# McPiFace-60mmFan-V3.net
KiCad netlist of a schematic drawn in EAGLE
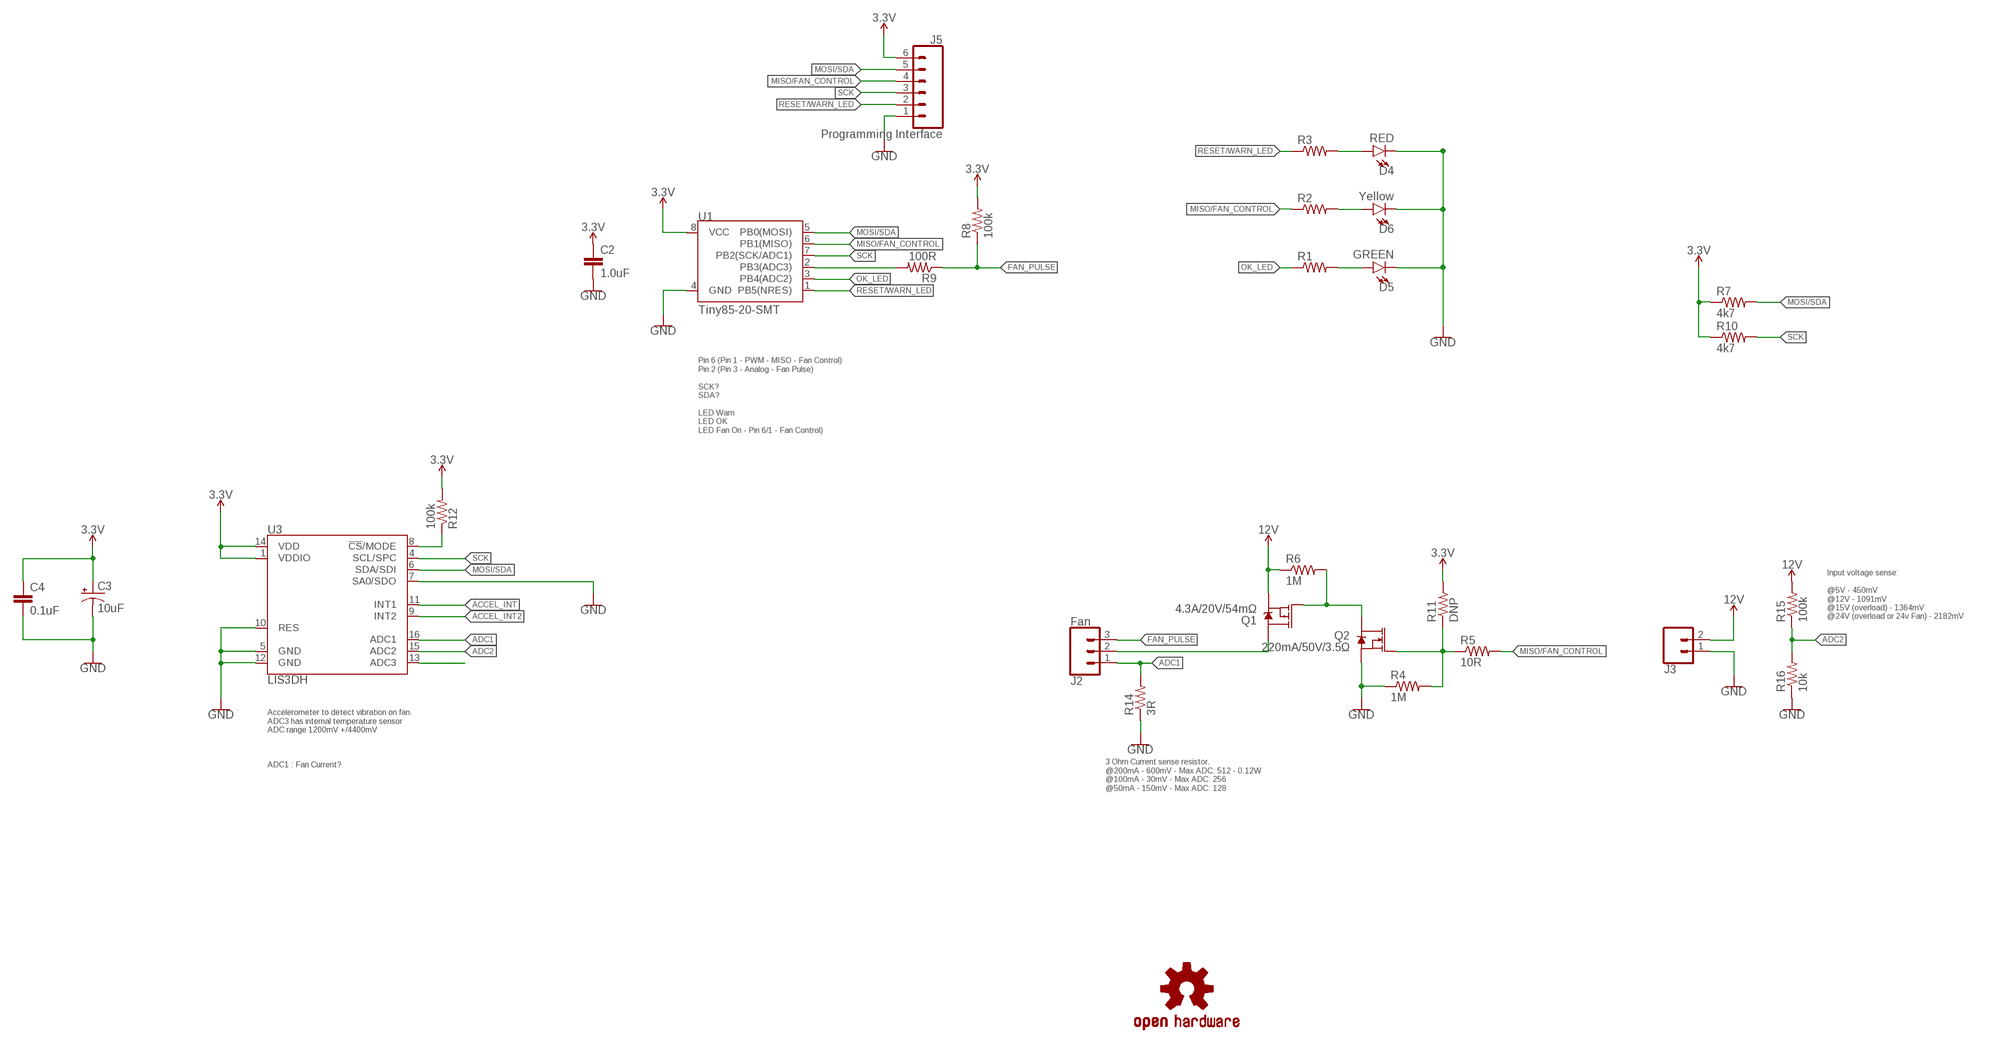
[diagram p0: schematic, sheet 1]

(export (version "E")
  (design (tool "Eeschema 10.0.6"))
  (components
    (comp (ref "C2")
      (value "1.0uF")
      (footprint "eagle-import:0805")
      (libsource (lib "eagle-import") (part "1.0UF-0805-25V-10%"))
    )
    (comp (ref "C3")
      (value "10uF")
      (footprint "eagle-import:EIA3216")
      (libsource (lib "eagle-import") (part "10UF-16V-10%(TANT)"))
    )
    (comp (ref "C4")
      (value "0.1uF")
      (footprint "eagle-import:0805")
      (libsource (lib "eagle-import") (part "1.0UF-0805-25V-10%"))
    )
    (comp (ref "D4")
      (value "RED")
      (footprint "eagle-import:LED-1206")
      (libsource (lib "eagle-import") (part "LED-RED1206"))
    )
    (comp (ref "D5")
      (value "GREEN")
      (footprint "eagle-import:LED-1206")
      (libsource (lib "eagle-import") (part "LED-GREEN1206"))
    )
    (comp (ref "D6")
      (value "Yellow")
      (footprint "eagle-import:LED-1206")
      (libsource (lib "eagle-import") (part "LED-YELLOWLILYPAD"))
    )
    (comp (ref "J2")
      (value "Fan")
      (footprint "eagle-import:JST-3-SMD")
      (fields (field (name "MFG") "S3B-PH-SM4-TB(LF)(SN)"))
      (libsource (lib "eagle-import") (part "CONN_03JST-SMD"))
    )
    (comp (ref "J3")
      (value "CONN_02-JST-2MM-SMT")
      (footprint "eagle-import:JST-2-SMD")
      (fields (field (name "MFG") "S2B-PH-SM4-TB(LF)(SN)"))
      (libsource (lib "eagle-import") (part "CONN_02-JST-2MM-SMT"))
    )
    (comp (ref "J5")
      (value "Programming Interface")
      (footprint "eagle-import:1X06-1MM")
      (libsource (lib "eagle-import") (part "CONN_06SMD-1MM"))
    )
    (comp (ref "LOGO1")
      (value "OSHW-LOGOL")
      (footprint "eagle-import:OSHW-LOGO-L")
      (libsource (lib "eagle-import") (part "OSHW-LOGOL"))
    )
    (comp (ref "Q1")
      (value "4.3A/20V/54mΩ")
      (footprint "eagle-import:SOT23-3")
      (libsource (lib "eagle-import") (part "MOSFET_PCH-IRLML2244"))
    )
    (comp (ref "Q2")
      (value "220mA/50V/3.5Ω")
      (footprint "eagle-import:SOT23-3")
      (libsource (lib "eagle-import") (part "MOSFET-NCH-BSS138"))
    )
    (comp (ref "R1")
      (value "RESISTOR0805-RES")
      (footprint "eagle-import:0805")
      (libsource (lib "eagle-import") (part "RESISTOR0805-RES"))
    )
    (comp (ref "R2")
      (value "RESISTOR0805-RES")
      (footprint "eagle-import:0805")
      (libsource (lib "eagle-import") (part "RESISTOR0805-RES"))
    )
    (comp (ref "R3")
      (value "RESISTOR0805-RES")
      (footprint "eagle-import:0805")
      (libsource (lib "eagle-import") (part "RESISTOR0805-RES"))
    )
    (comp (ref "R4")
      (value "1M")
      (footprint "eagle-import:0805")
      (libsource (lib "eagle-import") (part "RESISTOR0805-RES"))
    )
    (comp (ref "R5")
      (value "10R")
      (footprint "eagle-import:0805")
      (libsource (lib "eagle-import") (part "RESISTOR0805-RES"))
    )
    (comp (ref "R6")
      (value "1M")
      (footprint "eagle-import:0805")
      (libsource (lib "eagle-import") (part "RESISTOR0805-RES"))
    )
    (comp (ref "R7")
      (value "4k7")
      (footprint "eagle-import:0805")
      (libsource (lib "eagle-import") (part "RESISTOR0805-RES"))
    )
    (comp (ref "R8")
      (value "100k")
      (footprint "eagle-import:0805")
      (libsource (lib "eagle-import") (part "RESISTOR0805-RES"))
    )
    (comp (ref "R9")
      (value "100R")
      (footprint "eagle-import:0805")
      (libsource (lib "eagle-import") (part "RESISTOR0805-RES"))
    )
    (comp (ref "R10")
      (value "4k7")
      (footprint "eagle-import:0805")
      (libsource (lib "eagle-import") (part "RESISTOR0805-RES"))
    )
    (comp (ref "R11")
      (value "DNP")
      (footprint "eagle-import:0805")
      (libsource (lib "eagle-import") (part "RESISTOR0805-RES"))
    )
    (comp (ref "R12")
      (value "100k")
      (footprint "eagle-import:0805")
      (libsource (lib "eagle-import") (part "RESISTOR0805-RES"))
    )
    (comp (ref "R14")
      (value "3R")
      (footprint "eagle-import:0805")
      (libsource (lib "eagle-import") (part "RESISTOR0805-RES"))
    )
    (comp (ref "R15")
      (value "100k")
      (footprint "eagle-import:0805")
      (libsource (lib "eagle-import") (part "RESISTOR0805-RES"))
    )
    (comp (ref "R16")
      (value "10k")
      (footprint "eagle-import:0805")
      (libsource (lib "eagle-import") (part "RESISTOR0805-RES"))
    )
    (comp (ref "U1")
      (value "Tiny85-20-SMT")
      (footprint "eagle-import:SO08-EIAJ")
      (libsource (lib "eagle-import") (part "ATTINY45TINY85-20-SMT"))
    )
    (comp (ref "U3")
      (value "LIS3DH")
      (footprint "eagle-import:LGA-16-3X3")
      (libsource (lib "eagle-import") (part "LIS3DH"))
    )
  )
  (nets
    (net (code "1") (name "3.3V") (class "Default")
      (node (ref "C2") (pin "1") (pinfunction "1_1") (pintype "passive"))
      (node (ref "C3") (pin "A") (pinfunction "+_A") (pintype "passive"))
      (node (ref "C4") (pin "1") (pinfunction "1_1") (pintype "passive"))
      (node (ref "J5") (pin "6") (pinfunction "6_6") (pintype "passive"))
      (node (ref "R10") (pin "1") (pinfunction "1_1") (pintype "passive"))
      (node (ref "R11") (pin "2") (pinfunction "2_2") (pintype "passive"))
      (node (ref "R12") (pin "2") (pinfunction "2_2") (pintype "passive"))
      (node (ref "R7") (pin "1") (pinfunction "1_1") (pintype "passive"))
      (node (ref "R8") (pin "2") (pinfunction "2_2") (pintype "passive"))
      (node (ref "U1") (pin "8") (pinfunction "VCC_8") (pintype "bidirectional"))
      (node (ref "U3") (pin "1") (pinfunction "VDDIO_1") (pintype "bidirectional"))
      (node (ref "U3") (pin "14") (pinfunction "VDD_14") (pintype "bidirectional"))
    )
    (net (code "2") (name "12V") (class "Default")
      (node (ref "J3") (pin "2") (pinfunction "1_2") (pintype "passive"))
      (node (ref "Q1") (pin "2") (pinfunction "S_2") (pintype "bidirectional"))
      (node (ref "R15") (pin "2") (pinfunction "2_2") (pintype "passive"))
      (node (ref "R6") (pin "1") (pinfunction "1_1") (pintype "passive"))
    )
    (net (code "3") (name "ACCEL_INT") (class "Default")
      (node (ref "U3") (pin "11") (pinfunction "INT1_11") (pintype "bidirectional"))
    )
    (net (code "4") (name "ACCEL_INT2") (class "Default")
      (node (ref "U3") (pin "9") (pinfunction "INT2_9") (pintype "bidirectional"))
    )
    (net (code "5") (name "ADC1") (class "Default")
      (node (ref "J2") (pin "1") (pinfunction "3_1") (pintype "passive"))
      (node (ref "R14") (pin "2") (pinfunction "2_2") (pintype "passive"))
      (node (ref "U3") (pin "16") (pinfunction "ADC1_16") (pintype "bidirectional"))
    )
    (net (code "6") (name "ADC2") (class "Default")
      (node (ref "R15") (pin "1") (pinfunction "1_1") (pintype "passive"))
      (node (ref "R16") (pin "2") (pinfunction "2_2") (pintype "passive"))
      (node (ref "U3") (pin "15") (pinfunction "ADC2_15") (pintype "bidirectional"))
    )
    (net (code "7") (name "FAN_PULSE") (class "Default")
      (node (ref "J2") (pin "3") (pinfunction "1_3") (pintype "passive"))
      (node (ref "R8") (pin "1") (pinfunction "1_1") (pintype "passive"))
      (node (ref "R9") (pin "1") (pinfunction "1_1") (pintype "passive"))
    )
    (net (code "8") (name "GND") (class "Default")
      (node (ref "C2") (pin "2") (pinfunction "2_2") (pintype "passive"))
      (node (ref "C3") (pin "C") (pinfunction "-_C") (pintype "passive"))
      (node (ref "C4") (pin "2") (pinfunction "2_2") (pintype "passive"))
      (node (ref "D4") (pin "C") (pinfunction "C_C") (pintype "passive"))
      (node (ref "D5") (pin "C") (pinfunction "C_C") (pintype "passive"))
      (node (ref "D6") (pin "C") (pinfunction "C_C") (pintype "passive"))
      (node (ref "J3") (pin "1") (pinfunction "2_1") (pintype "passive"))
      (node (ref "J5") (pin "1") (pinfunction "1_1") (pintype "passive"))
      (node (ref "Q2") (pin "2") (pinfunction "S_2") (pintype "bidirectional"))
      (node (ref "R14") (pin "1") (pinfunction "1_1") (pintype "passive"))
      (node (ref "R16") (pin "1") (pinfunction "1_1") (pintype "passive"))
      (node (ref "R4") (pin "1") (pinfunction "1_1") (pintype "passive"))
      (node (ref "U1") (pin "4") (pinfunction "GND_4") (pintype "bidirectional"))
      (node (ref "U3") (pin "10") (pinfunction "RES_10") (pintype "bidirectional"))
      (node (ref "U3") (pin "12") (pinfunction "GND_12") (pintype "bidirectional"))
      (node (ref "U3") (pin "5") (pinfunction "GND_5") (pintype "bidirectional"))
      (node (ref "U3") (pin "7") (pinfunction "SA0/SDO_7") (pintype "bidirectional"))
    )
    (net (code "9") (name "MISO{slash}FAN_CONTROL") (class "Default")
      (node (ref "J5") (pin "4") (pinfunction "4_4") (pintype "passive"))
      (node (ref "R2") (pin "1") (pinfunction "1_1") (pintype "passive"))
      (node (ref "R5") (pin "2") (pinfunction "2_2") (pintype "passive"))
      (node (ref "U1") (pin "6") (pinfunction "PB1(MISO)_6") (pintype "bidirectional"))
    )
    (net (code "10") (name "MOSI{slash}SDA") (class "Default")
      (node (ref "J5") (pin "5") (pinfunction "5_5") (pintype "passive"))
      (node (ref "R7") (pin "2") (pinfunction "2_2") (pintype "passive"))
      (node (ref "U1") (pin "5") (pinfunction "PB0(MOSI)_5") (pintype "bidirectional"))
      (node (ref "U3") (pin "6") (pinfunction "SDA/SDI_6") (pintype "bidirectional"))
    )
    (net (code "11") (name "Net-(D4-PadA)") (class "Default")
      (node (ref "D4") (pin "A") (pinfunction "A_A") (pintype "passive"))
      (node (ref "R3") (pin "2") (pinfunction "2_2") (pintype "passive"))
    )
    (net (code "12") (name "Net-(D5-PadA)") (class "Default")
      (node (ref "D5") (pin "A") (pinfunction "A_A") (pintype "passive"))
      (node (ref "R1") (pin "2") (pinfunction "2_2") (pintype "passive"))
    )
    (net (code "13") (name "Net-(D6-PadA)") (class "Default")
      (node (ref "D6") (pin "A") (pinfunction "A_A") (pintype "passive"))
      (node (ref "R2") (pin "2") (pinfunction "2_2") (pintype "passive"))
    )
    (net (code "14") (name "Net-(Q1-D)") (class "Default")
      (node (ref "J2") (pin "2") (pinfunction "2_2") (pintype "passive"))
      (node (ref "Q1") (pin "3") (pinfunction "D_3") (pintype "bidirectional"))
    )
    (net (code "15") (name "Net-(Q1-G)") (class "Default")
      (node (ref "Q1") (pin "1") (pinfunction "G_1") (pintype "bidirectional"))
      (node (ref "Q2") (pin "3") (pinfunction "D_3") (pintype "bidirectional"))
      (node (ref "R6") (pin "2") (pinfunction "2_2") (pintype "passive"))
    )
    (net (code "16") (name "Net-(Q2-G)") (class "Default")
      (node (ref "Q2") (pin "1") (pinfunction "G_1") (pintype "bidirectional"))
      (node (ref "R11") (pin "1") (pinfunction "1_1") (pintype "passive"))
      (node (ref "R4") (pin "2") (pinfunction "2_2") (pintype "passive"))
      (node (ref "R5") (pin "1") (pinfunction "1_1") (pintype "passive"))
    )
    (net (code "17") (name "Net-(U1-PB3(ADC3))") (class "Default")
      (node (ref "R9") (pin "2") (pinfunction "2_2") (pintype "passive"))
      (node (ref "U1") (pin "2") (pinfunction "PB3(ADC3)_2") (pintype "bidirectional"))
    )
    (net (code "18") (name "Net-(U3-~{CS}{slash}MODE)") (class "Default")
      (node (ref "R12") (pin "1") (pinfunction "1_1") (pintype "passive"))
      (node (ref "U3") (pin "8") (pinfunction "~{CS}/MODE_8") (pintype "bidirectional"))
    )
    (net (code "19") (name "OK_LED") (class "Default")
      (node (ref "R1") (pin "1") (pinfunction "1_1") (pintype "passive"))
      (node (ref "U1") (pin "3") (pinfunction "PB4(ADC2)_3") (pintype "bidirectional"))
    )
    (net (code "20") (name "RESET{slash}WARN_LED") (class "Default")
      (node (ref "J5") (pin "2") (pinfunction "2_2") (pintype "passive"))
      (node (ref "R3") (pin "1") (pinfunction "1_1") (pintype "passive"))
      (node (ref "U1") (pin "1") (pinfunction "PB5(NRES)_1") (pintype "bidirectional"))
    )
    (net (code "21") (name "SCK") (class "Default")
      (node (ref "J5") (pin "3") (pinfunction "3_3") (pintype "passive"))
      (node (ref "R10") (pin "2") (pinfunction "2_2") (pintype "passive"))
      (node (ref "U1") (pin "7") (pinfunction "PB2(SCK/ADC1)_7") (pintype "bidirectional"))
      (node (ref "U3") (pin "4") (pinfunction "SCL/SPC_4") (pintype "bidirectional"))
    )
    (net (code "22") (name "unconnected-(U3-ADC3-Pad13)") (class "Default")
      (node (ref "U3") (pin "13") (pinfunction "ADC3_13") (pintype "bidirectional"))
    )
  )
)
